# codm-wifi-pixel-controller.net
KiCad netlist of a schematic drawn in EAGLE
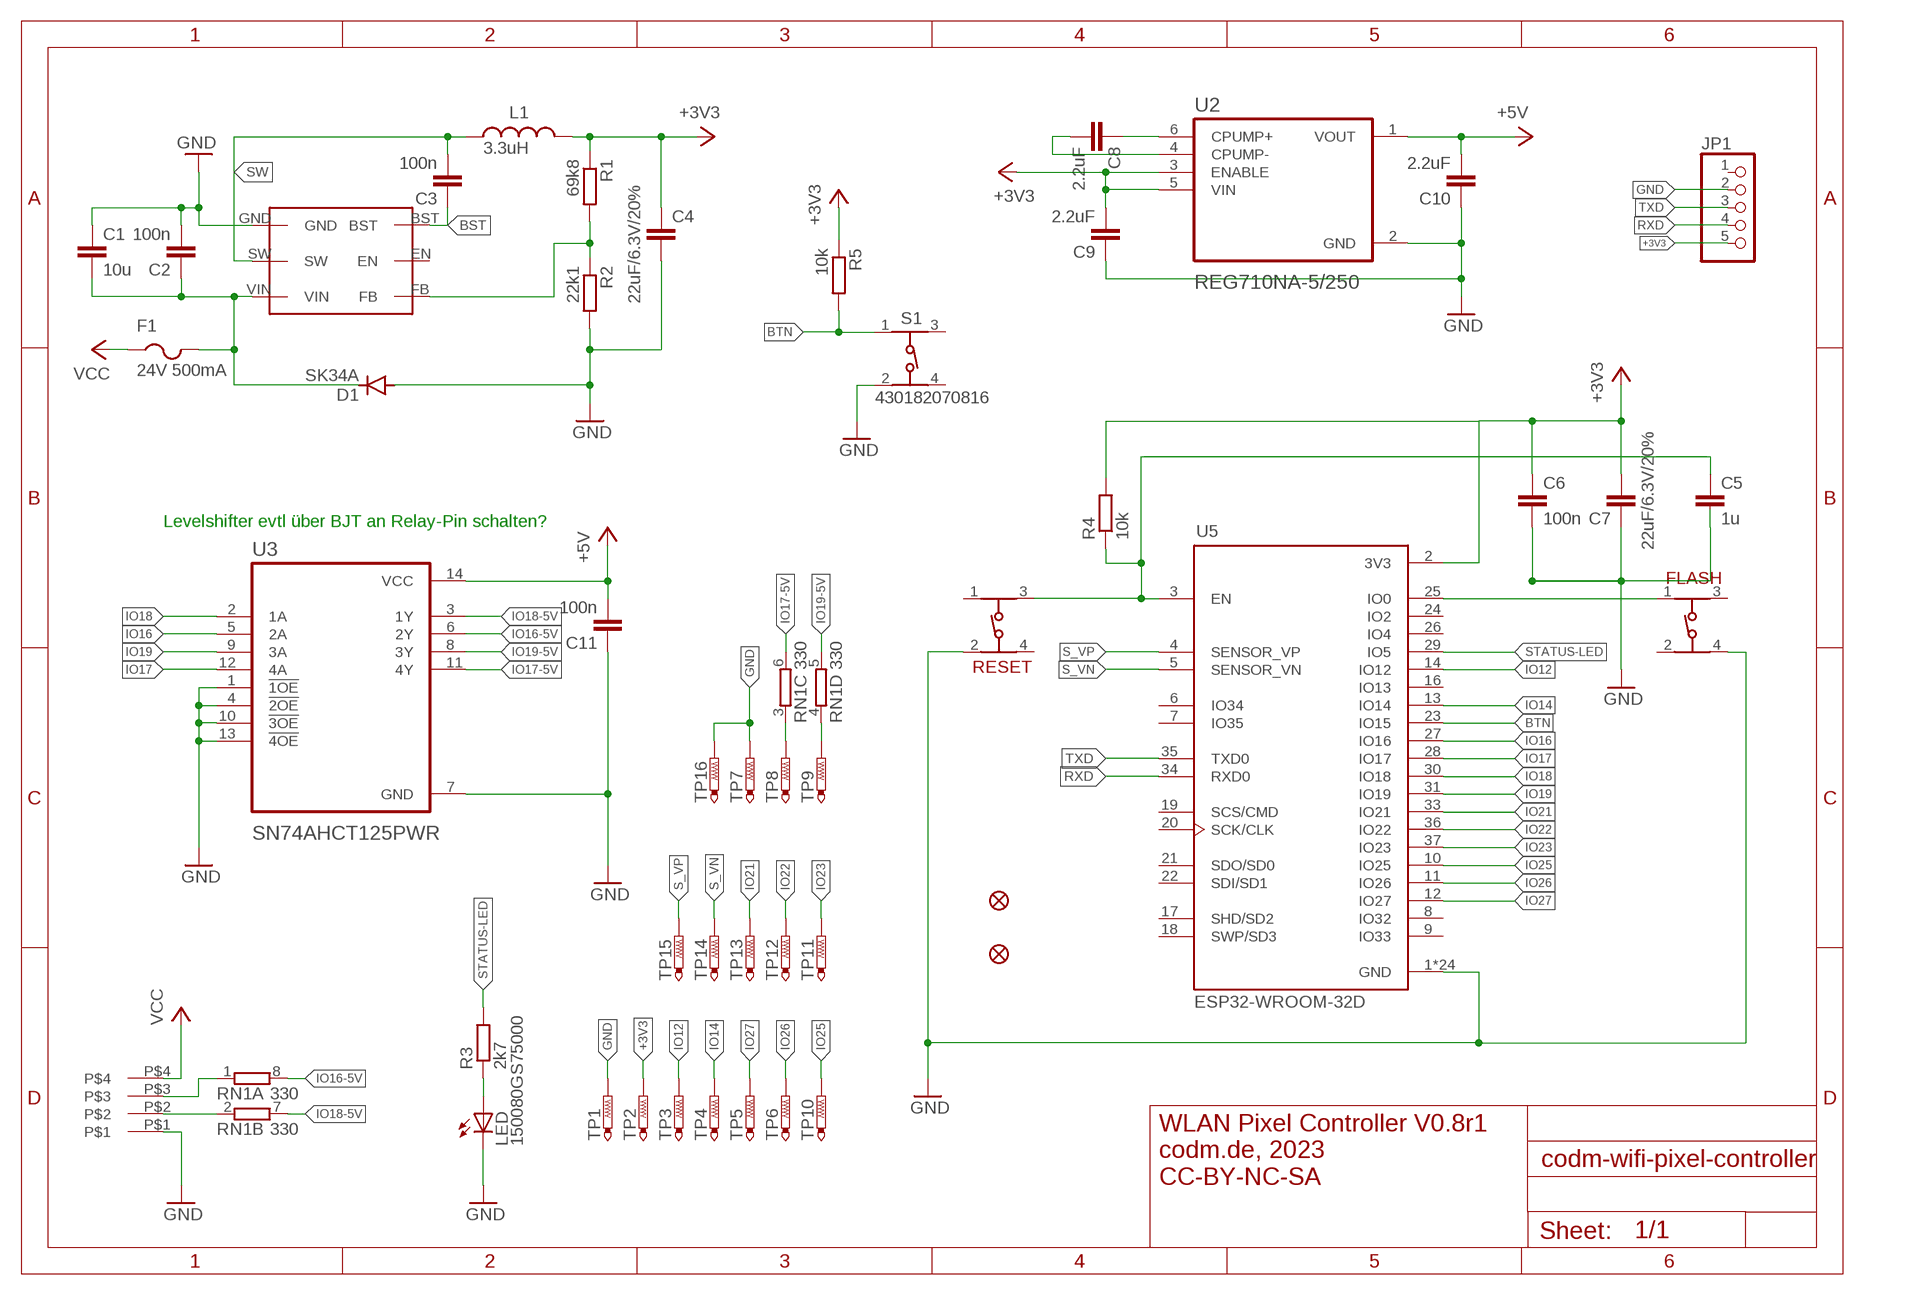
[diagram p0: schematic, sheet 1]

(export (version "E")
  (design (tool "Eeschema 10.0.6"))
  (components
    (comp (ref "C1")
      (value "10u")
      (footprint "eagle-import:C0805K")
      (libsource (lib "eagle-import") (part "rcl_334_C-EUC0805K"))
    )
    (comp (ref "C2")
      (value "100n")
      (footprint "eagle-import:C0603K")
      (libsource (lib "eagle-import") (part "C-EUC0603K"))
    )
    (comp (ref "C3")
      (value "100n")
      (footprint "eagle-import:C0603K")
      (libsource (lib "eagle-import") (part "C-EUC0603K"))
    )
    (comp (ref "C4")
      (value "22uF/6.3V/20%")
      (footprint "eagle-import:C0805K")
      (libsource (lib "eagle-import") (part "rcl_334_C-EUC0805K"))
    )
    (comp (ref "C5")
      (value "1u")
      (footprint "eagle-import:C0603K")
      (libsource (lib "eagle-import") (part "C-EUC0603K"))
    )
    (comp (ref "C6")
      (value "100n")
      (footprint "eagle-import:C0603K")
      (libsource (lib "eagle-import") (part "C-EUC0603K"))
    )
    (comp (ref "C7")
      (value "22uF/6.3V/20%")
      (footprint "eagle-import:C0805K")
      (libsource (lib "eagle-import") (part "rcl_334_C-EUC0805K"))
    )
    (comp (ref "C8")
      (value "2.2uF")
      (footprint "eagle-import:C0603K")
      (libsource (lib "eagle-import") (part "C-EUC0603K"))
    )
    (comp (ref "C9")
      (value "2.2uF")
      (footprint "eagle-import:C0603K")
      (libsource (lib "eagle-import") (part "C-EUC0603K"))
    )
    (comp (ref "C10")
      (value "2.2uF")
      (footprint "eagle-import:C0603K")
      (libsource (lib "eagle-import") (part "C-EUC0603K"))
    )
    (comp (ref "C11")
      (value "100n")
      (footprint "eagle-import:C0603K")
      (libsource (lib "eagle-import") (part "C-EUC0603K"))
    )
    (comp (ref "D1")
      (value "SK34A")
      (footprint "eagle-import:DO214AC")
      (libsource (lib "eagle-import") (part "DIODE-DO214AC"))
    )
    (comp (ref "F1")
      (value "24V 500mA")
      (footprint "eagle-import:R1206")
      (libsource (lib "eagle-import") (part "PTCFUSE-1206"))
    )
    (comp (ref "FD1")
      (value "FIDUCIAL1X2")
      (footprint "eagle-import:FIDUCIAL-1X2")
      (libsource (lib "eagle-import") (part "FIDUCIAL1X2"))
    )
    (comp (ref "FD2")
      (value "FIDUCIAL1X2")
      (footprint "eagle-import:FIDUCIAL-1X2")
      (libsource (lib "eagle-import") (part "FIDUCIAL1X2"))
    )
    (comp (ref "FLASH")
      (value "434153017835")
      (footprint "eagle-import:434153017835")
      (libsource (lib "eagle-import") (part "434153017835"))
    )
    (comp (ref "JP1")
      (value "PINHD-1X5")
      (footprint "eagle-import:1X05")
      (libsource (lib "eagle-import") (part "PINHD-1X5"))
    )
    (comp (ref "L1")
      (value "3.3uH")
      (footprint "eagle-import:WE-LQ_1812")
      (libsource (lib "eagle-import") (part "WE-LQ_1812_744045003"))
    )
    (comp (ref "LED")
      (value "150080GS75000")
      (footprint "eagle-import:CHIP-LED0805")
      (libsource (lib "eagle-import") (part "LEDCHIP-LED0805"))
    )
    (comp (ref "R1")
      (value "69k8")
      (footprint "eagle-import:R0603")
      (libsource (lib "eagle-import") (part "R-EU_R0603"))
    )
    (comp (ref "R2")
      (value "22k1")
      (footprint "eagle-import:R0603")
      (libsource (lib "eagle-import") (part "R-EU_R0603"))
    )
    (comp (ref "R3")
      (value "2k7")
      (footprint "eagle-import:R0603")
      (libsource (lib "eagle-import") (part "R-EU_R0603"))
    )
    (comp (ref "R4")
      (value "10k")
      (footprint "eagle-import:R0603")
      (libsource (lib "eagle-import") (part "R-EU_R0603"))
    )
    (comp (ref "R5")
      (value "10k")
      (footprint "eagle-import:R0603")
      (libsource (lib "eagle-import") (part "R-EU_R0603"))
    )
    (comp (ref "RESET")
      (value "434153017835")
      (footprint "eagle-import:434153017835")
      (libsource (lib "eagle-import") (part "434153017835"))
    )
    (comp (ref "RN1")
      (value "330")
      (footprint "eagle-import:EXB38V")
      (libsource (lib "eagle-import") (part "4R-NEXB38V"))
    )
    (comp (ref "S1")
      (value "430182070816")
      (footprint "eagle-import:430182070816")
      (libsource (lib "eagle-import") (part "430182070816"))
    )
    (comp (ref "TP1")
      (value "PTR1TP14R")
      (footprint "eagle-import:TP14R")
      (libsource (lib "eagle-import") (part "PTR1TP14R"))
    )
    (comp (ref "TP2")
      (value "PTR1TP14R")
      (footprint "eagle-import:TP14R")
      (libsource (lib "eagle-import") (part "PTR1TP14R"))
    )
    (comp (ref "TP3")
      (value "PTR1TP14R")
      (footprint "eagle-import:TP14R")
      (libsource (lib "eagle-import") (part "PTR1TP14R"))
    )
    (comp (ref "TP4")
      (value "PTR1TP14R")
      (footprint "eagle-import:TP14R")
      (libsource (lib "eagle-import") (part "PTR1TP14R"))
    )
    (comp (ref "TP5")
      (value "PTR1TP14R")
      (footprint "eagle-import:TP14R")
      (libsource (lib "eagle-import") (part "PTR1TP14R"))
    )
    (comp (ref "TP6")
      (value "PTR1TP14R")
      (footprint "eagle-import:TP14R")
      (libsource (lib "eagle-import") (part "PTR1TP14R"))
    )
    (comp (ref "TP7")
      (value "PTR1TP14R")
      (footprint "eagle-import:TP14R")
      (libsource (lib "eagle-import") (part "PTR1TP14R"))
    )
    (comp (ref "TP8")
      (value "PTR1TP14R")
      (footprint "eagle-import:TP14R")
      (libsource (lib "eagle-import") (part "PTR1TP14R"))
    )
    (comp (ref "TP9")
      (value "PTR1TP14R")
      (footprint "eagle-import:TP14R")
      (libsource (lib "eagle-import") (part "PTR1TP14R"))
    )
    (comp (ref "TP10")
      (value "PTR1TP14R")
      (footprint "eagle-import:TP14R")
      (libsource (lib "eagle-import") (part "PTR1TP14R"))
    )
    (comp (ref "TP11")
      (value "PTR1TP14R")
      (footprint "eagle-import:TP14R")
      (libsource (lib "eagle-import") (part "PTR1TP14R"))
    )
    (comp (ref "TP12")
      (value "PTR1TP14R")
      (footprint "eagle-import:TP14R")
      (libsource (lib "eagle-import") (part "PTR1TP14R"))
    )
    (comp (ref "TP13")
      (value "PTR1TP14R")
      (footprint "eagle-import:TP14R")
      (libsource (lib "eagle-import") (part "PTR1TP14R"))
    )
    (comp (ref "TP14")
      (value "PTR1TP14R")
      (footprint "eagle-import:TP14R")
      (libsource (lib "eagle-import") (part "PTR1TP14R"))
    )
    (comp (ref "TP15")
      (value "PTR1TP14R")
      (footprint "eagle-import:TP14R")
      (libsource (lib "eagle-import") (part "PTR1TP14R"))
    )
    (comp (ref "TP16")
      (value "PTR1TP14R")
      (footprint "eagle-import:TP14R")
      (libsource (lib "eagle-import") (part "PTR1TP14R"))
    )
    (comp (ref "U$101")
      (value "MCV-1,5/4-G-3,81")
      (footprint "eagle-import:MCV-1,5_4-G-3,81")
      (libsource (lib "eagle-import") (part "MCV-1,5/4-G-3,81"))
    )
    (comp (ref "U1")
      (value "AP62XXX-TSOT26")
      (footprint "eagle-import:AP62XXX-TSOT26")
      (libsource (lib "eagle-import") (part "AP62XXX-TSOT26"))
    )
    (comp (ref "U2")
      (value "REG710NA-5/250")
      (footprint "eagle-import:SOT95P280X145-6N")
      (fields (field (name "MF") "Texas Instruments"))
      (libsource (lib "eagle-import") (part "REG710NA-5/250"))
    )
    (comp (ref "U3")
      (value "SN74AHCT125PWR")
      (footprint "eagle-import:SOP65P640X120-14N")
      (fields (field (name "MF") "Texas Instruments"))
      (libsource (lib "eagle-import") (part "SN74AHCT125PWR"))
    )
    (comp (ref "U5")
      (value "ESP32-WROOM-32D")
      (footprint "eagle-import:MODULE_ESP32-WROOM-32D")
      (fields (field (name "MF") "Espressif Systems"))
      (libsource (lib "eagle-import") (part "ESP32-WROOM-32D"))
    )
  )
  (nets
    (net (code "1") (name "+3V3") (class "Default")
      (node (ref "C4") (pin "1") (pinfunction "1_1") (pintype "passive"))
      (node (ref "C6") (pin "1") (pinfunction "1_1") (pintype "passive"))
      (node (ref "C7") (pin "2") (pinfunction "2_2") (pintype "passive"))
      (node (ref "C9") (pin "2") (pinfunction "2_2") (pintype "passive"))
      (node (ref "JP1") (pin "5") (pinfunction "5_5") (pintype "passive"))
      (node (ref "L1") (pin "2") (pinfunction "2_2") (pintype "passive"))
      (node (ref "R1") (pin "1") (pinfunction "1_1") (pintype "passive"))
      (node (ref "R4") (pin "2") (pinfunction "2_2") (pintype "passive"))
      (node (ref "R5") (pin "1") (pinfunction "1_1") (pintype "passive"))
      (node (ref "TP2") (pin "TP") (pinfunction "TP_TP") (pintype "input"))
      (node (ref "U2") (pin "3") (pinfunction "ENABLE_3") (pintype "input"))
      (node (ref "U2") (pin "5") (pinfunction "VIN_5") (pintype "input"))
      (node (ref "U5") (pin "2") (pinfunction "3V3_2") (pintype "power_in"))
    )
    (net (code "2") (name "+5V") (class "Default")
      (node (ref "C10") (pin "2") (pinfunction "2_2") (pintype "passive"))
      (node (ref "C11") (pin "2") (pinfunction "2_2") (pintype "passive"))
      (node (ref "U2") (pin "1") (pinfunction "VOUT_1") (pintype "output"))
      (node (ref "U3") (pin "14") (pinfunction "VCC_14") (pintype "power_in"))
    )
    (net (code "3") (name "BST") (class "Default")
      (node (ref "C3") (pin "1") (pinfunction "1_1") (pintype "passive"))
      (node (ref "U1") (pin "BST") (pinfunction "BST_BST") (pintype "bidirectional"))
    )
    (net (code "4") (name "BTN") (class "Default")
      (node (ref "R5") (pin "2") (pinfunction "2_2") (pintype "passive"))
      (node (ref "S1") (pin "1") (pinfunction "1_1") (pintype "passive"))
      (node (ref "U5") (pin "23") (pinfunction "IO15_23") (pintype "bidirectional"))
    )
    (net (code "5") (name "GND") (class "Default")
      (node (ref "C1") (pin "1") (pinfunction "1_1") (pintype "passive"))
      (node (ref "C10") (pin "1") (pinfunction "1_1") (pintype "passive"))
      (node (ref "C11") (pin "1") (pinfunction "1_1") (pintype "passive"))
      (node (ref "C2") (pin "2") (pinfunction "2_2") (pintype "passive"))
      (node (ref "C4") (pin "2") (pinfunction "2_2") (pintype "passive"))
      (node (ref "C5") (pin "2") (pinfunction "2_2") (pintype "passive"))
      (node (ref "C6") (pin "2") (pinfunction "2_2") (pintype "passive"))
      (node (ref "C7") (pin "1") (pinfunction "1_1") (pintype "passive"))
      (node (ref "C9") (pin "1") (pinfunction "1_1") (pintype "passive"))
      (node (ref "D1") (pin "A") (pinfunction "A_A") (pintype "passive"))
      (node (ref "FLASH") (pin "4") (pinfunction "4_4") (pintype "passive"))
      (node (ref "JP1") (pin "2") (pinfunction "2_2") (pintype "passive"))
      (node (ref "LED") (pin "C") (pinfunction "C_C") (pintype "passive"))
      (node (ref "R2") (pin "2") (pinfunction "2_2") (pintype "passive"))
      (node (ref "RESET") (pin "2") (pinfunction "3_2") (pintype "passive"))
      (node (ref "S1") (pin "2") (pinfunction "2_2") (pintype "passive"))
      (node (ref "TP1") (pin "TP") (pinfunction "TP_TP") (pintype "input"))
      (node (ref "TP16") (pin "TP") (pinfunction "TP_TP") (pintype "input"))
      (node (ref "TP7") (pin "TP") (pinfunction "TP_TP") (pintype "input"))
      (node (ref "U$101") (pin "P$1") (pinfunction "P$1_P$1") (pintype "bidirectional"))
      (node (ref "U1") (pin "GND") (pinfunction "GND_GND") (pintype "bidirectional"))
      (node (ref "U2") (pin "2") (pinfunction "GND_2") (pintype "power_in"))
      (node (ref "U3") (pin "1") (pinfunction "~{1OE}_1") (pintype "input"))
      (node (ref "U3") (pin "10") (pinfunction "~{3OE}_10") (pintype "input"))
      (node (ref "U3") (pin "13") (pinfunction "~{4OE}_13") (pintype "input"))
      (node (ref "U3") (pin "4") (pinfunction "~{2OE}_4") (pintype "input"))
      (node (ref "U3") (pin "7") (pinfunction "GND_7") (pintype "power_in"))
      (node (ref "U5") (pin "1") (pinfunction "GND_1") (pintype "power_in"))
      (node (ref "U5") (pin "15") (pinfunction "GND_15") (pintype "power_in"))
      (node (ref "U5") (pin "38") (pinfunction "GND_38") (pintype "power_in"))
      (node (ref "U5") (pin "39_1") (pinfunction "GND_39_1") (pintype "power_in"))
      (node (ref "U5") (pin "39_10") (pinfunction "GND_39_10") (pintype "power_in"))
      (node (ref "U5") (pin "39_11") (pinfunction "GND_39_11") (pintype "power_in"))
      (node (ref "U5") (pin "39_12") (pinfunction "GND_39_12") (pintype "power_in"))
      (node (ref "U5") (pin "39_13") (pinfunction "GND_39_13") (pintype "power_in"))
      (node (ref "U5") (pin "39_14") (pinfunction "GND_39_14") (pintype "power_in"))
      (node (ref "U5") (pin "39_15") (pinfunction "GND_39_15") (pintype "power_in"))
      (node (ref "U5") (pin "39_16") (pinfunction "GND_39_16") (pintype "power_in"))
      (node (ref "U5") (pin "39_17") (pinfunction "GND_39_17") (pintype "power_in"))
      (node (ref "U5") (pin "39_18") (pinfunction "GND_39_18") (pintype "power_in"))
      (node (ref "U5") (pin "39_19") (pinfunction "GND_39_19") (pintype "power_in"))
      (node (ref "U5") (pin "39_2") (pinfunction "GND_39_2") (pintype "power_in"))
      (node (ref "U5") (pin "39_20") (pinfunction "GND_39_20") (pintype "power_in"))
      (node (ref "U5") (pin "39_21") (pinfunction "GND_39_21") (pintype "power_in"))
      (node (ref "U5") (pin "39_3") (pinfunction "GND_39_3") (pintype "power_in"))
      (node (ref "U5") (pin "39_4") (pinfunction "GND_39_4") (pintype "power_in"))
      (node (ref "U5") (pin "39_5") (pinfunction "GND_39_5") (pintype "power_in"))
      (node (ref "U5") (pin "39_6") (pinfunction "GND_39_6") (pintype "power_in"))
      (node (ref "U5") (pin "39_7") (pinfunction "GND_39_7") (pintype "power_in"))
      (node (ref "U5") (pin "39_8") (pinfunction "GND_39_8") (pintype "power_in"))
      (node (ref "U5") (pin "39_9") (pinfunction "GND_39_9") (pintype "power_in"))
    )
    (net (code "6") (name "IO12") (class "Default")
      (node (ref "TP3") (pin "TP") (pinfunction "TP_TP") (pintype "input"))
      (node (ref "U5") (pin "14") (pinfunction "IO12_14") (pintype "bidirectional"))
    )
    (net (code "7") (name "IO14") (class "Default")
      (node (ref "TP4") (pin "TP") (pinfunction "TP_TP") (pintype "input"))
      (node (ref "U5") (pin "13") (pinfunction "IO14_13") (pintype "bidirectional"))
    )
    (net (code "8") (name "IO16") (class "Default")
      (node (ref "U3") (pin "5") (pinfunction "2A_5") (pintype "input"))
      (node (ref "U5") (pin "27") (pinfunction "IO16_27") (pintype "bidirectional"))
    )
    (net (code "9") (name "IO16-5V") (class "Default")
      (node (ref "RN1") (pin "8") (pinfunction "2_8") (pintype "passive"))
      (node (ref "U3") (pin "6") (pinfunction "2Y_6") (pintype "output"))
    )
    (net (code "10") (name "IO17") (class "Default")
      (node (ref "U3") (pin "12") (pinfunction "4A_12") (pintype "input"))
      (node (ref "U5") (pin "28") (pinfunction "IO17_28") (pintype "bidirectional"))
    )
    (net (code "11") (name "IO17-5V") (class "Default")
      (node (ref "RN1") (pin "6") (pinfunction "2_6") (pintype "passive"))
      (node (ref "U3") (pin "11") (pinfunction "4Y_11") (pintype "output"))
    )
    (net (code "12") (name "IO18") (class "Default")
      (node (ref "U3") (pin "2") (pinfunction "1A_2") (pintype "input"))
      (node (ref "U5") (pin "30") (pinfunction "IO18_30") (pintype "bidirectional"))
    )
    (net (code "13") (name "IO18-5V") (class "Default")
      (node (ref "RN1") (pin "7") (pinfunction "2_7") (pintype "passive"))
      (node (ref "U3") (pin "3") (pinfunction "1Y_3") (pintype "output"))
    )
    (net (code "14") (name "IO19") (class "Default")
      (node (ref "U3") (pin "9") (pinfunction "3A_9") (pintype "input"))
      (node (ref "U5") (pin "31") (pinfunction "IO19_31") (pintype "bidirectional"))
    )
    (net (code "15") (name "IO19-5V") (class "Default")
      (node (ref "RN1") (pin "5") (pinfunction "2_5") (pintype "passive"))
      (node (ref "U3") (pin "8") (pinfunction "3Y_8") (pintype "output"))
    )
    (net (code "16") (name "IO21") (class "Default")
      (node (ref "TP13") (pin "TP") (pinfunction "TP_TP") (pintype "input"))
      (node (ref "U5") (pin "33") (pinfunction "IO21_33") (pintype "bidirectional"))
    )
    (net (code "17") (name "IO22") (class "Default")
      (node (ref "TP12") (pin "TP") (pinfunction "TP_TP") (pintype "input"))
      (node (ref "U5") (pin "36") (pinfunction "IO22_36") (pintype "bidirectional"))
    )
    (net (code "18") (name "IO23") (class "Default")
      (node (ref "TP11") (pin "TP") (pinfunction "TP_TP") (pintype "input"))
      (node (ref "U5") (pin "37") (pinfunction "IO23_37") (pintype "bidirectional"))
    )
    (net (code "19") (name "IO25") (class "Default")
      (node (ref "TP10") (pin "TP") (pinfunction "TP_TP") (pintype "input"))
      (node (ref "U5") (pin "10") (pinfunction "IO25_10") (pintype "bidirectional"))
    )
    (net (code "20") (name "IO26") (class "Default")
      (node (ref "TP6") (pin "TP") (pinfunction "TP_TP") (pintype "input"))
      (node (ref "U5") (pin "11") (pinfunction "IO26_11") (pintype "bidirectional"))
    )
    (net (code "21") (name "IO27") (class "Default")
      (node (ref "TP5") (pin "TP") (pinfunction "TP_TP") (pintype "input"))
      (node (ref "U5") (pin "12") (pinfunction "IO27_12") (pintype "bidirectional"))
    )
    (net (code "22") (name "Net-(C1-Pad2)") (class "Default")
      (node (ref "C1") (pin "2") (pinfunction "2_2") (pintype "passive"))
      (node (ref "C2") (pin "1") (pinfunction "1_1") (pintype "passive"))
      (node (ref "D1") (pin "C") (pinfunction "C_C") (pintype "passive"))
      (node (ref "F1") (pin "2") (pinfunction "2_2") (pintype "passive"))
      (node (ref "U1") (pin "VIN") (pinfunction "VIN_VIN") (pintype "bidirectional"))
    )
    (net (code "23") (name "Net-(LED-PadA)") (class "Default")
      (node (ref "LED") (pin "A") (pinfunction "A_A") (pintype "passive"))
      (node (ref "R3") (pin "1") (pinfunction "1_1") (pintype "passive"))
    )
    (net (code "24") (name "Net-(R1-Pad2)") (class "Default")
      (node (ref "R1") (pin "2") (pinfunction "2_2") (pintype "passive"))
      (node (ref "R2") (pin "1") (pinfunction "1_1") (pintype "passive"))
      (node (ref "U1") (pin "FB") (pinfunction "FB_FB") (pintype "bidirectional"))
    )
    (net (code "25") (name "Net-(RESET-2)") (class "Default")
      (node (ref "C5") (pin "1") (pinfunction "1_1") (pintype "passive"))
      (node (ref "R4") (pin "1") (pinfunction "1_1") (pintype "passive"))
      (node (ref "RESET") (pin "3") (pinfunction "2_3") (pintype "passive"))
      (node (ref "U5") (pin "3") (pinfunction "EN_3") (pintype "input"))
    )
    (net (code "26") (name "Net-(RN1-Pad1)") (class "Default")
      (node (ref "RN1") (pin "1") (pinfunction "1_1") (pintype "passive"))
      (node (ref "U$101") (pin "P$3") (pinfunction "P$3_P$3") (pintype "bidirectional"))
    )
    (net (code "27") (name "Net-(RN1B-1)") (class "Default")
      (node (ref "RN1") (pin "2") (pinfunction "1_2") (pintype "passive"))
      (node (ref "U$101") (pin "P$2") (pinfunction "P$2_P$2") (pintype "bidirectional"))
    )
    (net (code "28") (name "Net-(RN1C-1)") (class "Default")
      (node (ref "RN1") (pin "3") (pinfunction "1_3") (pintype "passive"))
      (node (ref "TP8") (pin "TP") (pinfunction "TP_TP") (pintype "input"))
    )
    (net (code "29") (name "Net-(RN1D-1)") (class "Default")
      (node (ref "RN1") (pin "4") (pinfunction "1_4") (pintype "passive"))
      (node (ref "TP9") (pin "TP") (pinfunction "TP_TP") (pintype "input"))
    )
    (net (code "30") (name "Net-(U2-CPUMP+)") (class "Default")
      (node (ref "C8") (pin "1") (pinfunction "1_1") (pintype "passive"))
      (node (ref "U2") (pin "6") (pinfunction "CPUMP+_6") (pintype "input"))
    )
    (net (code "31") (name "Net-(U2-CPUMP-)") (class "Default")
      (node (ref "C8") (pin "2") (pinfunction "2_2") (pintype "passive"))
      (node (ref "U2") (pin "4") (pinfunction "CPUMP-_4") (pintype "input"))
    )
    (net (code "32") (name "Net-(U5-IO0)") (class "Default")
      (node (ref "FLASH") (pin "1") (pinfunction "1_1") (pintype "passive"))
      (node (ref "U5") (pin "25") (pinfunction "IO0_25") (pintype "bidirectional"))
    )
    (net (code "33") (name "RXD") (class "Default")
      (node (ref "JP1") (pin "4") (pinfunction "4_4") (pintype "passive"))
      (node (ref "U5") (pin "34") (pinfunction "RXD0_34") (pintype "bidirectional"))
    )
    (net (code "34") (name "STATUS-LED") (class "Default")
      (node (ref "R3") (pin "2") (pinfunction "2_2") (pintype "passive"))
      (node (ref "U5") (pin "29") (pinfunction "IO5_29") (pintype "bidirectional"))
    )
    (net (code "35") (name "SW") (class "Default")
      (node (ref "C3") (pin "2") (pinfunction "2_2") (pintype "passive"))
      (node (ref "L1") (pin "1") (pinfunction "1_1") (pintype "passive"))
      (node (ref "U1") (pin "SW") (pinfunction "SW_SW") (pintype "bidirectional"))
    )
    (net (code "36") (name "S_VN") (class "Default")
      (node (ref "TP14") (pin "TP") (pinfunction "TP_TP") (pintype "input"))
      (node (ref "U5") (pin "5") (pinfunction "SENSOR_VN_5") (pintype "input"))
    )
    (net (code "37") (name "S_VP") (class "Default")
      (node (ref "TP15") (pin "TP") (pinfunction "TP_TP") (pintype "input"))
      (node (ref "U5") (pin "4") (pinfunction "SENSOR_VP_4") (pintype "input"))
    )
    (net (code "38") (name "TXD") (class "Default")
      (node (ref "JP1") (pin "3") (pinfunction "3_3") (pintype "passive"))
      (node (ref "U5") (pin "35") (pinfunction "TXD0_35") (pintype "bidirectional"))
    )
    (net (code "39") (name "VCC") (class "Default")
      (node (ref "F1") (pin "1") (pinfunction "1_1") (pintype "passive"))
      (node (ref "U$101") (pin "P$4") (pinfunction "P$4_P$4") (pintype "bidirectional"))
    )
    (net (code "40") (name "unconnected-(FLASH-2-Pad3)") (class "Default")
      (node (ref "FLASH") (pin "3") (pinfunction "2_3") (pintype "passive"))
    )
    (net (code "41") (name "unconnected-(FLASH-3-Pad2)") (class "Default")
      (node (ref "FLASH") (pin "2") (pinfunction "3_2") (pintype "passive"))
    )
    (net (code "42") (name "unconnected-(JP1-Pad1)") (class "Default")
      (node (ref "JP1") (pin "1") (pinfunction "1_1") (pintype "passive"))
    )
    (net (code "43") (name "unconnected-(RESET-Pad1)") (class "Default")
      (node (ref "RESET") (pin "1") (pinfunction "1_1") (pintype "passive"))
    )
    (net (code "44") (name "unconnected-(RESET-Pad4)") (class "Default")
      (node (ref "RESET") (pin "4") (pinfunction "4_4") (pintype "passive"))
    )
    (net (code "45") (name "unconnected-(S1-Pad3)") (class "Default")
      (node (ref "S1") (pin "3") (pinfunction "3_3") (pintype "passive"))
    )
    (net (code "46") (name "unconnected-(S1-Pad4)") (class "Default")
      (node (ref "S1") (pin "4") (pinfunction "4_4") (pintype "passive"))
    )
    (net (code "47") (name "unconnected-(U1-PadEN)") (class "Default")
      (node (ref "U1") (pin "EN") (pinfunction "EN_EN") (pintype "bidirectional"))
    )
    (net (code "48") (name "unconnected-(U5-IO2-Pad24)") (class "Default")
      (node (ref "U5") (pin "24") (pinfunction "IO2_24") (pintype "bidirectional"))
    )
    (net (code "49") (name "unconnected-(U5-IO4-Pad26)") (class "Default")
      (node (ref "U5") (pin "26") (pinfunction "IO4_26") (pintype "bidirectional"))
    )
    (net (code "50") (name "unconnected-(U5-IO13-Pad16)") (class "Default")
      (node (ref "U5") (pin "16") (pinfunction "IO13_16") (pintype "bidirectional"))
    )
    (net (code "51") (name "unconnected-(U5-IO32-Pad8)") (class "Default")
      (node (ref "U5") (pin "8") (pinfunction "IO32_8") (pintype "bidirectional"))
    )
    (net (code "52") (name "unconnected-(U5-IO33-Pad9)") (class "Default")
      (node (ref "U5") (pin "9") (pinfunction "IO33_9") (pintype "bidirectional"))
    )
    (net (code "53") (name "unconnected-(U5-IO34-Pad6)") (class "Default")
      (node (ref "U5") (pin "6") (pinfunction "IO34_6") (pintype "input"))
    )
    (net (code "54") (name "unconnected-(U5-IO35-Pad7)") (class "Default")
      (node (ref "U5") (pin "7") (pinfunction "IO35_7") (pintype "input"))
    )
    (net (code "55") (name "unconnected-(U5-SCK{slash}CLK-Pad20)") (class "Default")
      (node (ref "U5") (pin "20") (pinfunction "SCK/CLK_20") (pintype "bidirectional"))
    )
    (net (code "56") (name "unconnected-(U5-SCS{slash}CMD-Pad19)") (class "Default")
      (node (ref "U5") (pin "19") (pinfunction "SCS/CMD_19") (pintype "bidirectional"))
    )
    (net (code "57") (name "unconnected-(U5-SDI{slash}SD1-Pad22)") (class "Default")
      (node (ref "U5") (pin "22") (pinfunction "SDI/SD1_22") (pintype "bidirectional"))
    )
    (net (code "58") (name "unconnected-(U5-SDO{slash}SD0-Pad21)") (class "Default")
      (node (ref "U5") (pin "21") (pinfunction "SDO/SD0_21") (pintype "bidirectional"))
    )
    (net (code "59") (name "unconnected-(U5-SHD{slash}SD2-Pad17)") (class "Default")
      (node (ref "U5") (pin "17") (pinfunction "SHD/SD2_17") (pintype "bidirectional"))
    )
    (net (code "60") (name "unconnected-(U5-SWP{slash}SD3-Pad18)") (class "Default")
      (node (ref "U5") (pin "18") (pinfunction "SWP/SD3_18") (pintype "bidirectional"))
    )
  )
)
